# PWM.net
KiCad netlist of a schematic drawn in EAGLE
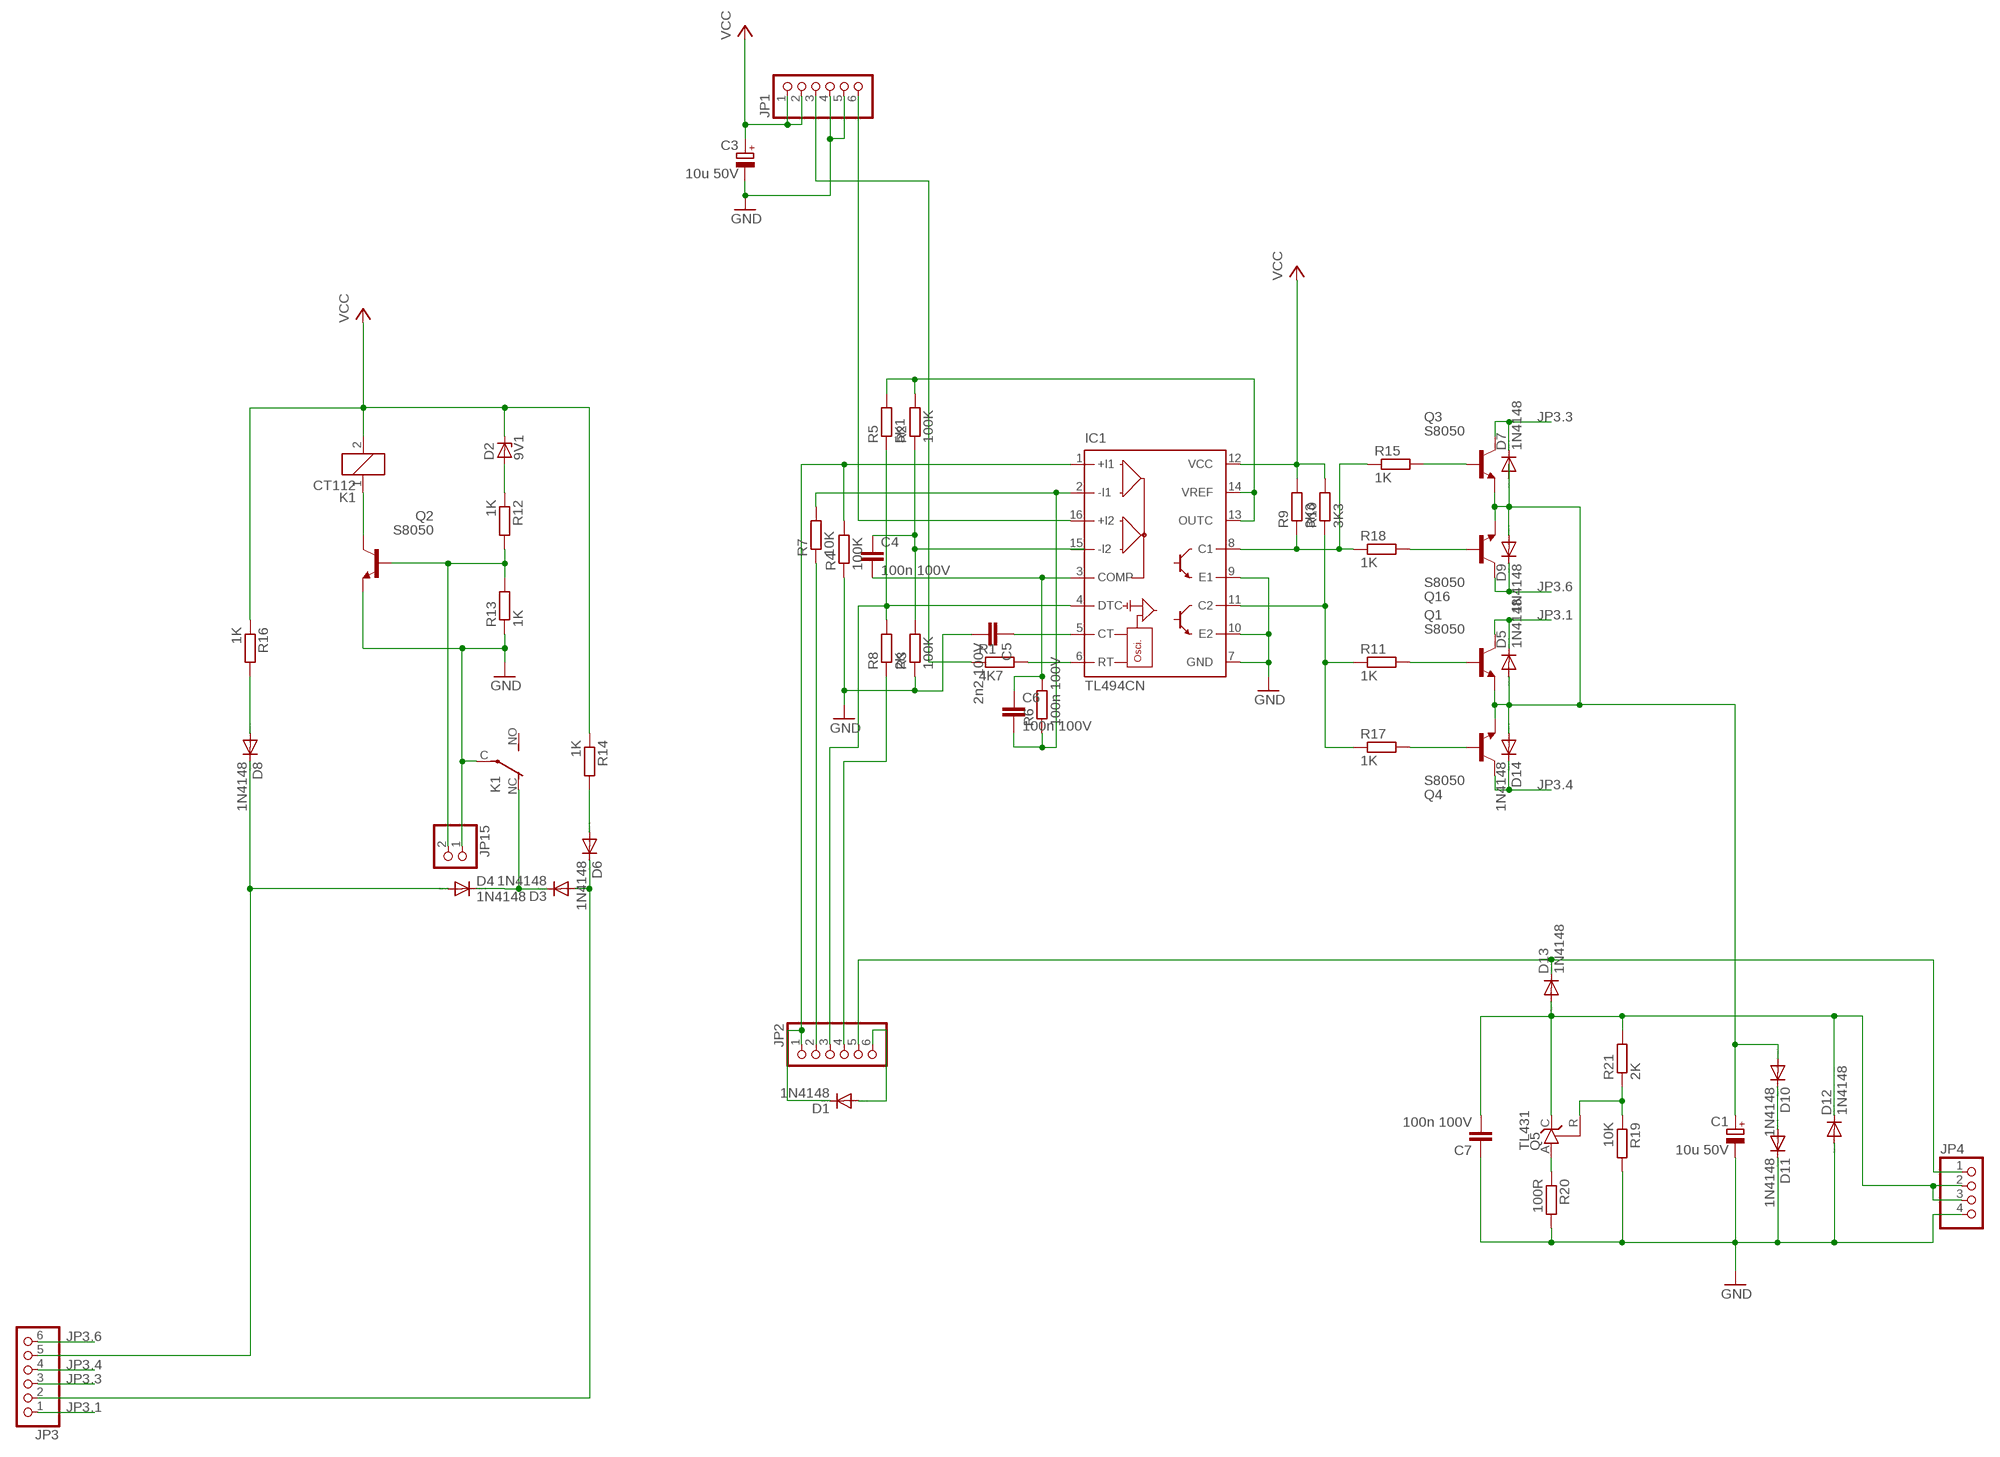
[diagram p0: schematic, sheet 1]

(export (version "E")
  (design (tool "Eeschema 10.0.6"))
  (components
    (comp (ref "C1")
      (value "10u 50V")
      (footprint "eagle-import:E2,5-5")
      (libsource (lib "eagle-import") (part "CPOL-EUE2.5-5"))
    )
    (comp (ref "C3")
      (value "10u 50V")
      (footprint "eagle-import:E2,5-5")
      (libsource (lib "eagle-import") (part "CPOL-EUE2.5-5"))
    )
    (comp (ref "C4")
      (value "100n 100V")
      (footprint "eagle-import:C1206")
      (libsource (lib "eagle-import") (part "C-EUC1206"))
    )
    (comp (ref "C5")
      (value "2n2 100V")
      (footprint "eagle-import:C1206")
      (libsource (lib "eagle-import") (part "C-EUC1206"))
    )
    (comp (ref "C6")
      (value "100n 100V")
      (footprint "eagle-import:C1206")
      (libsource (lib "eagle-import") (part "C-EUC1206"))
    )
    (comp (ref "C7")
      (value "100n 100V")
      (footprint "eagle-import:C1206")
      (libsource (lib "eagle-import") (part "C-EUC1206"))
    )
    (comp (ref "D1")
      (value "1N4148")
      (footprint "eagle-import:MINIMELF")
      (libsource (lib "eagle-import") (part "DIODE-MINIMELF"))
    )
    (comp (ref "D2")
      (value "9V1")
      (footprint "eagle-import:SOD80C")
      (libsource (lib "eagle-import") (part "ZENER-DIODESOD80C"))
    )
    (comp (ref "D3")
      (value "1N4148")
      (footprint "eagle-import:MINIMELF")
      (libsource (lib "eagle-import") (part "DIODE-MINIMELF"))
    )
    (comp (ref "D4")
      (value "1N4148")
      (footprint "eagle-import:MINIMELF")
      (libsource (lib "eagle-import") (part "DIODE-MINIMELF"))
    )
    (comp (ref "D5")
      (value "1N4148")
      (footprint "eagle-import:MINIMELF")
      (libsource (lib "eagle-import") (part "DIODE-MINIMELF"))
    )
    (comp (ref "D6")
      (value "1N4148")
      (footprint "eagle-import:MINIMELF")
      (libsource (lib "eagle-import") (part "DIODE-MINIMELF"))
    )
    (comp (ref "D7")
      (value "1N4148")
      (footprint "eagle-import:MINIMELF")
      (libsource (lib "eagle-import") (part "DIODE-MINIMELF"))
    )
    (comp (ref "D8")
      (value "1N4148")
      (footprint "eagle-import:MINIMELF")
      (libsource (lib "eagle-import") (part "DIODE-MINIMELF"))
    )
    (comp (ref "D9")
      (value "1N4148")
      (footprint "eagle-import:MINIMELF")
      (libsource (lib "eagle-import") (part "DIODE-MINIMELF"))
    )
    (comp (ref "D10")
      (value "1N4148")
      (footprint "eagle-import:MINIMELF")
      (libsource (lib "eagle-import") (part "DIODE-MINIMELF"))
    )
    (comp (ref "D11")
      (value "1N4148")
      (footprint "eagle-import:MINIMELF")
      (libsource (lib "eagle-import") (part "DIODE-MINIMELF"))
    )
    (comp (ref "D12")
      (value "1N4148")
      (footprint "eagle-import:MINIMELF")
      (libsource (lib "eagle-import") (part "DIODE-MINIMELF"))
    )
    (comp (ref "D13")
      (value "1N4148")
      (footprint "eagle-import:MINIMELF")
      (libsource (lib "eagle-import") (part "DIODE-MINIMELF"))
    )
    (comp (ref "D14")
      (value "1N4148")
      (footprint "eagle-import:MINIMELF")
      (libsource (lib "eagle-import") (part "DIODE-MINIMELF"))
    )
    (comp (ref "IC1")
      (value "TL494CN")
      (footprint "eagle-import:DIL16")
      (libsource (lib "eagle-import") (part "TL494NC"))
    )
    (comp (ref "JP1")
      (value "PINHD-1X6")
      (footprint "eagle-import:1X06")
      (libsource (lib "eagle-import") (part "PINHD-1X6"))
    )
    (comp (ref "JP2")
      (value "PINHD-1X6")
      (footprint "eagle-import:1X06")
      (libsource (lib "eagle-import") (part "PINHD-1X6"))
    )
    (comp (ref "JP3")
      (value "PINHD-1X6")
      (footprint "eagle-import:1X06")
      (libsource (lib "eagle-import") (part "PINHD-1X6"))
    )
    (comp (ref "JP4")
      (value "PINHD-1X4")
      (footprint "eagle-import:1X04")
      (libsource (lib "eagle-import") (part "PINHD-1X4"))
    )
    (comp (ref "JP15")
      (value "PINHD-1X2")
      (footprint "eagle-import:1X02")
      (libsource (lib "eagle-import") (part "PINHD-1X2"))
    )
    (comp (ref "K1")
      (value "CT112")
      (footprint "eagle-import:CT-SLIM")
      (libsource (lib "eagle-import") (part "CT112"))
    )
    (comp (ref "Q1")
      (value "S8050")
      (footprint "eagle-import:SOT23-BEC")
      (libsource (lib "eagle-import") (part "BC817SMD-16LT1"))
    )
    (comp (ref "Q2")
      (value "S8050")
      (footprint "eagle-import:SOT23-BEC")
      (libsource (lib "eagle-import") (part "BC817SMD-16LT1"))
    )
    (comp (ref "Q3")
      (value "S8050")
      (footprint "eagle-import:SOT23-BEC")
      (libsource (lib "eagle-import") (part "BC817SMD-16LT1"))
    )
    (comp (ref "Q4")
      (value "S8050")
      (footprint "eagle-import:SOT23-BEC")
      (libsource (lib "eagle-import") (part "BC817SMD-16LT1"))
    )
    (comp (ref "Q5")
      (value "TL431")
      (footprint "eagle-import:SOT23-5")
      (libsource (lib "eagle-import") (part "TL431-IDBVR"))
    )
    (comp (ref "Q16")
      (value "S8050")
      (footprint "eagle-import:SOT23-BEC")
      (libsource (lib "eagle-import") (part "BC817SMD-16LT1"))
    )
    (comp (ref "R1")
      (value "4K7")
      (footprint "eagle-import:R1206")
      (libsource (lib "eagle-import") (part "R-EU_R1206"))
    )
    (comp (ref "R2")
      (value "100K")
      (footprint "eagle-import:R1206")
      (libsource (lib "eagle-import") (part "R-EU_R1206"))
    )
    (comp (ref "R3")
      (value "100K")
      (footprint "eagle-import:R1206")
      (libsource (lib "eagle-import") (part "R-EU_R1206"))
    )
    (comp (ref "R4")
      (value "100K")
      (footprint "eagle-import:R1206")
      (libsource (lib "eagle-import") (part "R-EU_R1206"))
    )
    (comp (ref "R5")
      (value "5K1")
      (footprint "eagle-import:R1206")
      (libsource (lib "eagle-import") (part "R-EU_R1206"))
    )
    (comp (ref "R6")
      (value "100n 100V")
      (footprint "eagle-import:R1206")
      (libsource (lib "eagle-import") (part "R-EU_R1206"))
    )
    (comp (ref "R7")
      (value "10K")
      (footprint "eagle-import:R1206")
      (libsource (lib "eagle-import") (part "R-EU_R1206"))
    )
    (comp (ref "R8")
      (value "2K")
      (footprint "eagle-import:R1206")
      (libsource (lib "eagle-import") (part "R-EU_R1206"))
    )
    (comp (ref "R9")
      (value "3K3")
      (footprint "eagle-import:R1206")
      (libsource (lib "eagle-import") (part "R-EU_R1206"))
    )
    (comp (ref "R10")
      (value "3K3")
      (footprint "eagle-import:R1206")
      (libsource (lib "eagle-import") (part "R-EU_R1206"))
    )
    (comp (ref "R11")
      (value "1K")
      (footprint "eagle-import:R1206")
      (libsource (lib "eagle-import") (part "R-EU_R1206"))
    )
    (comp (ref "R12")
      (value "1K")
      (footprint "eagle-import:R1206")
      (libsource (lib "eagle-import") (part "R-EU_R1206"))
    )
    (comp (ref "R13")
      (value "1K")
      (footprint "eagle-import:R1206")
      (libsource (lib "eagle-import") (part "R-EU_R1206"))
    )
    (comp (ref "R14")
      (value "1K")
      (footprint "eagle-import:R1206")
      (libsource (lib "eagle-import") (part "R-EU_R1206"))
    )
    (comp (ref "R15")
      (value "1K")
      (footprint "eagle-import:R1206")
      (libsource (lib "eagle-import") (part "R-EU_R1206"))
    )
    (comp (ref "R16")
      (value "1K")
      (footprint "eagle-import:R1206")
      (libsource (lib "eagle-import") (part "R-EU_R1206"))
    )
    (comp (ref "R17")
      (value "1K")
      (footprint "eagle-import:R1206")
      (libsource (lib "eagle-import") (part "R-EU_R1206"))
    )
    (comp (ref "R18")
      (value "1K")
      (footprint "eagle-import:R1206")
      (libsource (lib "eagle-import") (part "R-EU_R1206"))
    )
    (comp (ref "R19")
      (value "10K")
      (footprint "eagle-import:R1206")
      (libsource (lib "eagle-import") (part "R-EU_R1206"))
    )
    (comp (ref "R20")
      (value "100R")
      (footprint "eagle-import:R1206")
      (libsource (lib "eagle-import") (part "R-EU_R1206"))
    )
    (comp (ref "R21")
      (value "2K")
      (footprint "eagle-import:R1206")
      (libsource (lib "eagle-import") (part "R-EU_R1206"))
    )
  )
  (nets
    (net (code "1") (name "/JP3.1") (class "Default")
      (node (ref "D5") (pin "C") (pinfunction "C_C") (pintype "passive"))
      (node (ref "JP3") (pin "1") (pinfunction "1_1") (pintype "passive"))
      (node (ref "Q1") (pin "C") (pinfunction "C_C") (pintype "passive"))
    )
    (net (code "2") (name "/JP3.3") (class "Default")
      (node (ref "D7") (pin "C") (pinfunction "C_C") (pintype "passive"))
      (node (ref "JP3") (pin "3") (pinfunction "3_3") (pintype "passive"))
      (node (ref "Q3") (pin "C") (pinfunction "C_C") (pintype "passive"))
    )
    (net (code "3") (name "/JP3.4") (class "Default")
      (node (ref "D14") (pin "C") (pinfunction "C_C") (pintype "passive"))
      (node (ref "JP3") (pin "4") (pinfunction "4_4") (pintype "passive"))
      (node (ref "Q4") (pin "C") (pinfunction "C_C") (pintype "passive"))
    )
    (net (code "4") (name "/JP3.6") (class "Default")
      (node (ref "D9") (pin "C") (pinfunction "C_C") (pintype "passive"))
      (node (ref "JP3") (pin "6") (pinfunction "6_6") (pintype "passive"))
      (node (ref "Q16") (pin "C") (pinfunction "C_C") (pintype "passive"))
    )
    (net (code "5") (name "GND") (class "Default")
      (node (ref "C1") (pin "-") (pinfunction "-_-") (pintype "passive"))
      (node (ref "C3") (pin "-") (pinfunction "-_-") (pintype "passive"))
      (node (ref "C5") (pin "2") (pinfunction "2_2") (pintype "passive"))
      (node (ref "C7") (pin "1") (pinfunction "1_1") (pintype "passive"))
      (node (ref "D11") (pin "C") (pinfunction "C_C") (pintype "passive"))
      (node (ref "D12") (pin "A") (pinfunction "A_A") (pintype "passive"))
      (node (ref "IC1") (pin "10") (pinfunction "E2_10") (pintype "passive"))
      (node (ref "IC1") (pin "7") (pinfunction "GND_7") (pintype "power_in"))
      (node (ref "IC1") (pin "9") (pinfunction "E1_9") (pintype "passive"))
      (node (ref "JP1") (pin "4") (pinfunction "4_4") (pintype "passive"))
      (node (ref "JP1") (pin "5") (pinfunction "5_5") (pintype "passive"))
      (node (ref "JP15") (pin "1") (pinfunction "1_1") (pintype "passive"))
      (node (ref "JP4") (pin "4") (pinfunction "4_4") (pintype "passive"))
      (node (ref "K1") (pin "C") (pinfunction "P_C") (pintype "passive"))
      (node (ref "Q2") (pin "E") (pinfunction "E_E") (pintype "passive"))
      (node (ref "R13") (pin "1") (pinfunction "1_1") (pintype "passive"))
      (node (ref "R19") (pin "2") (pinfunction "2_2") (pintype "passive"))
      (node (ref "R20") (pin "2") (pinfunction "2_2") (pintype "passive"))
      (node (ref "R3") (pin "1") (pinfunction "1_1") (pintype "passive"))
      (node (ref "R4") (pin "1") (pinfunction "1_1") (pintype "passive"))
    )
    (net (code "6") (name "Net-(C1-Pad+)") (class "Default")
      (node (ref "C1") (pin "+") (pinfunction "+_+") (pintype "passive"))
      (node (ref "D10") (pin "A") (pinfunction "A_A") (pintype "passive"))
      (node (ref "D14") (pin "A") (pinfunction "A_A") (pintype "passive"))
      (node (ref "D5") (pin "A") (pinfunction "A_A") (pintype "passive"))
      (node (ref "D7") (pin "A") (pinfunction "A_A") (pintype "passive"))
      (node (ref "D9") (pin "A") (pinfunction "A_A") (pintype "passive"))
      (node (ref "Q1") (pin "E") (pinfunction "E_E") (pintype "passive"))
      (node (ref "Q16") (pin "E") (pinfunction "E_E") (pintype "passive"))
      (node (ref "Q3") (pin "E") (pinfunction "E_E") (pintype "passive"))
      (node (ref "Q4") (pin "E") (pinfunction "E_E") (pintype "passive"))
    )
    (net (code "7") (name "Net-(C4-Pad1)") (class "Default")
      (node (ref "C4") (pin "1") (pinfunction "1_1") (pintype "passive"))
      (node (ref "R2") (pin "1") (pinfunction "1_1") (pintype "passive"))
      (node (ref "R3") (pin "2") (pinfunction "2_2") (pintype "passive"))
    )
    (net (code "8") (name "Net-(C7-Pad2)") (class "Default")
      (node (ref "C7") (pin "2") (pinfunction "2_2") (pintype "passive"))
      (node (ref "D12") (pin "C") (pinfunction "C_C") (pintype "passive"))
      (node (ref "D13") (pin "A") (pinfunction "A_A") (pintype "passive"))
      (node (ref "JP4") (pin "2") (pinfunction "2_2") (pintype "passive"))
      (node (ref "JP4") (pin "3") (pinfunction "3_3") (pintype "passive"))
      (node (ref "Q5") (pin "C") (pinfunction "C_C") (pintype "passive"))
      (node (ref "R21") (pin "2") (pinfunction "2_2") (pintype "passive"))
    )
    (net (code "9") (name "Net-(D1-PadA)") (class "Default")
      (node (ref "D1") (pin "A") (pinfunction "A_A") (pintype "passive"))
      (node (ref "JP2") (pin "6") (pinfunction "6_6") (pintype "passive"))
    )
    (net (code "10") (name "Net-(D2-PadA)") (class "Default")
      (node (ref "D2") (pin "A") (pinfunction "A_A") (pintype "passive"))
      (node (ref "R12") (pin "1") (pinfunction "1_1") (pintype "passive"))
    )
    (net (code "11") (name "Net-(D3-PadA)") (class "Default")
      (node (ref "D3") (pin "A") (pinfunction "A_A") (pintype "passive"))
      (node (ref "D6") (pin "C") (pinfunction "C_C") (pintype "passive"))
      (node (ref "JP3") (pin "2") (pinfunction "2_2") (pintype "passive"))
    )
    (net (code "12") (name "Net-(D4-PadA)") (class "Default")
      (node (ref "D4") (pin "A") (pinfunction "A_A") (pintype "passive"))
      (node (ref "D8") (pin "C") (pinfunction "C_C") (pintype "passive"))
      (node (ref "JP3") (pin "5") (pinfunction "5_5") (pintype "passive"))
    )
    (net (code "13") (name "Net-(D6-PadA)") (class "Default")
      (node (ref "D6") (pin "A") (pinfunction "A_A") (pintype "passive"))
      (node (ref "R14") (pin "2") (pinfunction "2_2") (pintype "passive"))
    )
    (net (code "14") (name "Net-(D8-PadA)") (class "Default")
      (node (ref "D8") (pin "A") (pinfunction "A_A") (pintype "passive"))
      (node (ref "R16") (pin "2") (pinfunction "2_2") (pintype "passive"))
    )
    (net (code "15") (name "Net-(D10-PadC)") (class "Default")
      (node (ref "D10") (pin "C") (pinfunction "C_C") (pintype "passive"))
      (node (ref "D11") (pin "A") (pinfunction "A_A") (pintype "passive"))
    )
    (net (code "16") (name "Net-(D13-PadC)") (class "Default")
      (node (ref "D13") (pin "C") (pinfunction "C_C") (pintype "passive"))
      (node (ref "JP2") (pin "5") (pinfunction "5_5") (pintype "passive"))
      (node (ref "JP4") (pin "1") (pinfunction "1_1") (pintype "passive"))
    )
    (net (code "17") (name "Net-(IC1-+I1)") (class "Default")
      (node (ref "D1") (pin "C") (pinfunction "C_C") (pintype "passive"))
      (node (ref "IC1") (pin "1") (pinfunction "+I1_1") (pintype "input"))
      (node (ref "JP2") (pin "1") (pinfunction "1_1") (pintype "passive"))
      (node (ref "R4") (pin "2") (pinfunction "2_2") (pintype "passive"))
    )
    (net (code "18") (name "Net-(IC1-+I2)") (class "Default")
      (node (ref "IC1") (pin "16") (pinfunction "+I2_16") (pintype "input"))
      (node (ref "JP1") (pin "6") (pinfunction "6_6") (pintype "passive"))
    )
    (net (code "19") (name "Net-(IC1--I1)") (class "Default")
      (node (ref "C6") (pin "2") (pinfunction "2_2") (pintype "passive"))
      (node (ref "IC1") (pin "2") (pinfunction "-I1_2") (pintype "input"))
      (node (ref "R6") (pin "1") (pinfunction "1_1") (pintype "passive"))
      (node (ref "R7") (pin "2") (pinfunction "2_2") (pintype "passive"))
    )
    (net (code "20") (name "Net-(IC1-C1)") (class "Default")
      (node (ref "IC1") (pin "8") (pinfunction "C1_8") (pintype "passive"))
      (node (ref "R15") (pin "1") (pinfunction "1_1") (pintype "passive"))
      (node (ref "R18") (pin "1") (pinfunction "1_1") (pintype "passive"))
      (node (ref "R9") (pin "1") (pinfunction "1_1") (pintype "passive"))
    )
    (net (code "21") (name "Net-(IC1-C2)") (class "Default")
      (node (ref "IC1") (pin "11") (pinfunction "C2_11") (pintype "passive"))
      (node (ref "R10") (pin "1") (pinfunction "1_1") (pintype "passive"))
      (node (ref "R11") (pin "1") (pinfunction "1_1") (pintype "passive"))
      (node (ref "R17") (pin "1") (pinfunction "1_1") (pintype "passive"))
    )
    (net (code "22") (name "Net-(IC1-COMP)") (class "Default")
      (node (ref "C4") (pin "2") (pinfunction "2_2") (pintype "passive"))
      (node (ref "C6") (pin "1") (pinfunction "1_1") (pintype "passive"))
      (node (ref "IC1") (pin "3") (pinfunction "COMP_3") (pintype "passive"))
      (node (ref "R6") (pin "2") (pinfunction "2_2") (pintype "passive"))
    )
    (net (code "23") (name "Net-(IC1-CT)") (class "Default")
      (node (ref "C5") (pin "1") (pinfunction "1_1") (pintype "passive"))
      (node (ref "IC1") (pin "5") (pinfunction "CT_5") (pintype "input"))
    )
    (net (code "24") (name "Net-(IC1-DTC)") (class "Default")
      (node (ref "IC1") (pin "4") (pinfunction "DTC_4") (pintype "input"))
      (node (ref "JP2") (pin "3") (pinfunction "3_3") (pintype "passive"))
      (node (ref "R5") (pin "1") (pinfunction "1_1") (pintype "passive"))
      (node (ref "R8") (pin "2") (pinfunction "2_2") (pintype "passive"))
    )
    (net (code "25") (name "Net-(IC1-OUTC)") (class "Default")
      (node (ref "IC1") (pin "13") (pinfunction "OUTC_13") (pintype "output"))
      (node (ref "IC1") (pin "14") (pinfunction "VREF_14") (pintype "input"))
      (node (ref "R2") (pin "2") (pinfunction "2_2") (pintype "passive"))
      (node (ref "R5") (pin "2") (pinfunction "2_2") (pintype "passive"))
    )
    (net (code "26") (name "Net-(IC1-RT)") (class "Default")
      (node (ref "IC1") (pin "6") (pinfunction "RT_6") (pintype "input"))
      (node (ref "R1") (pin "2") (pinfunction "2_2") (pintype "passive"))
    )
    (net (code "27") (name "Net-(JP1-Pad3)") (class "Default")
      (node (ref "JP1") (pin "3") (pinfunction "3_3") (pintype "passive"))
      (node (ref "R1") (pin "1") (pinfunction "1_1") (pintype "passive"))
    )
    (net (code "28") (name "Net-(JP2-Pad2)") (class "Default")
      (node (ref "JP2") (pin "2") (pinfunction "2_2") (pintype "passive"))
      (node (ref "R7") (pin "1") (pinfunction "1_1") (pintype "passive"))
    )
    (net (code "29") (name "Net-(JP2-Pad4)") (class "Default")
      (node (ref "JP2") (pin "4") (pinfunction "4_4") (pintype "passive"))
      (node (ref "R8") (pin "1") (pinfunction "1_1") (pintype "passive"))
    )
    (net (code "30") (name "Net-(JP15-Pad2)") (class "Default")
      (node (ref "JP15") (pin "2") (pinfunction "2_2") (pintype "passive"))
      (node (ref "Q2") (pin "B") (pinfunction "B_B") (pintype "passive"))
      (node (ref "R12") (pin "2") (pinfunction "2_2") (pintype "passive"))
      (node (ref "R13") (pin "2") (pinfunction "2_2") (pintype "passive"))
    )
    (net (code "31") (name "Net-(K1-Pad1)") (class "Default")
      (node (ref "K1") (pin "1") (pinfunction "1_1") (pintype "passive"))
      (node (ref "Q2") (pin "C") (pinfunction "C_C") (pintype "passive"))
    )
    (net (code "32") (name "Net-(K1B-O)") (class "Default")
      (node (ref "D3") (pin "C") (pinfunction "C_C") (pintype "passive"))
      (node (ref "D4") (pin "C") (pinfunction "C_C") (pintype "passive"))
      (node (ref "K1") (pin "NC") (pinfunction "O_NC") (pintype "passive"))
    )
    (net (code "33") (name "Net-(Q1-PadB)") (class "Default")
      (node (ref "Q1") (pin "B") (pinfunction "B_B") (pintype "passive"))
      (node (ref "R11") (pin "2") (pinfunction "2_2") (pintype "passive"))
    )
    (net (code "34") (name "Net-(Q3-PadB)") (class "Default")
      (node (ref "Q3") (pin "B") (pinfunction "B_B") (pintype "passive"))
      (node (ref "R15") (pin "2") (pinfunction "2_2") (pintype "passive"))
    )
    (net (code "35") (name "Net-(Q4-PadB)") (class "Default")
      (node (ref "Q4") (pin "B") (pinfunction "B_B") (pintype "passive"))
      (node (ref "R17") (pin "2") (pinfunction "2_2") (pintype "passive"))
    )
    (net (code "36") (name "Net-(Q5-PadA)") (class "Default")
      (node (ref "Q5") (pin "A") (pinfunction "A_A") (pintype "passive"))
      (node (ref "R20") (pin "1") (pinfunction "1_1") (pintype "passive"))
    )
    (net (code "37") (name "Net-(Q5-PadR)") (class "Default")
      (node (ref "Q5") (pin "R") (pinfunction "R_R") (pintype "passive"))
      (node (ref "R19") (pin "1") (pinfunction "1_1") (pintype "passive"))
      (node (ref "R21") (pin "1") (pinfunction "1_1") (pintype "passive"))
    )
    (net (code "38") (name "Net-(Q16-PadB)") (class "Default")
      (node (ref "Q16") (pin "B") (pinfunction "B_B") (pintype "passive"))
      (node (ref "R18") (pin "2") (pinfunction "2_2") (pintype "passive"))
    )
    (net (code "39") (name "VCC") (class "Default")
      (node (ref "C3") (pin "+") (pinfunction "+_+") (pintype "passive"))
      (node (ref "D2") (pin "C") (pinfunction "C_C") (pintype "passive"))
      (node (ref "IC1") (pin "12") (pinfunction "VCC_12") (pintype "power_in"))
      (node (ref "JP1") (pin "1") (pinfunction "1_1") (pintype "passive"))
      (node (ref "JP1") (pin "2") (pinfunction "2_2") (pintype "passive"))
      (node (ref "K1") (pin "2") (pinfunction "2_2") (pintype "passive"))
      (node (ref "R10") (pin "2") (pinfunction "2_2") (pintype "passive"))
      (node (ref "R14") (pin "1") (pinfunction "1_1") (pintype "passive"))
      (node (ref "R16") (pin "1") (pinfunction "1_1") (pintype "passive"))
      (node (ref "R9") (pin "2") (pinfunction "2_2") (pintype "passive"))
    )
    (net (code "40") (name "unconnected-(IC1--I2-Pad15)") (class "Default")
      (node (ref "IC1") (pin "15") (pinfunction "-I2_15") (pintype "input"))
    )
    (net (code "41") (name "unconnected-(K1B-S-PadNO)") (class "Default")
      (node (ref "K1") (pin "NO") (pinfunction "S_NO") (pintype "passive"))
    )
  )
)
